# PLC20_breakout.net
KiCad netlist of a schematic drawn in EAGLE
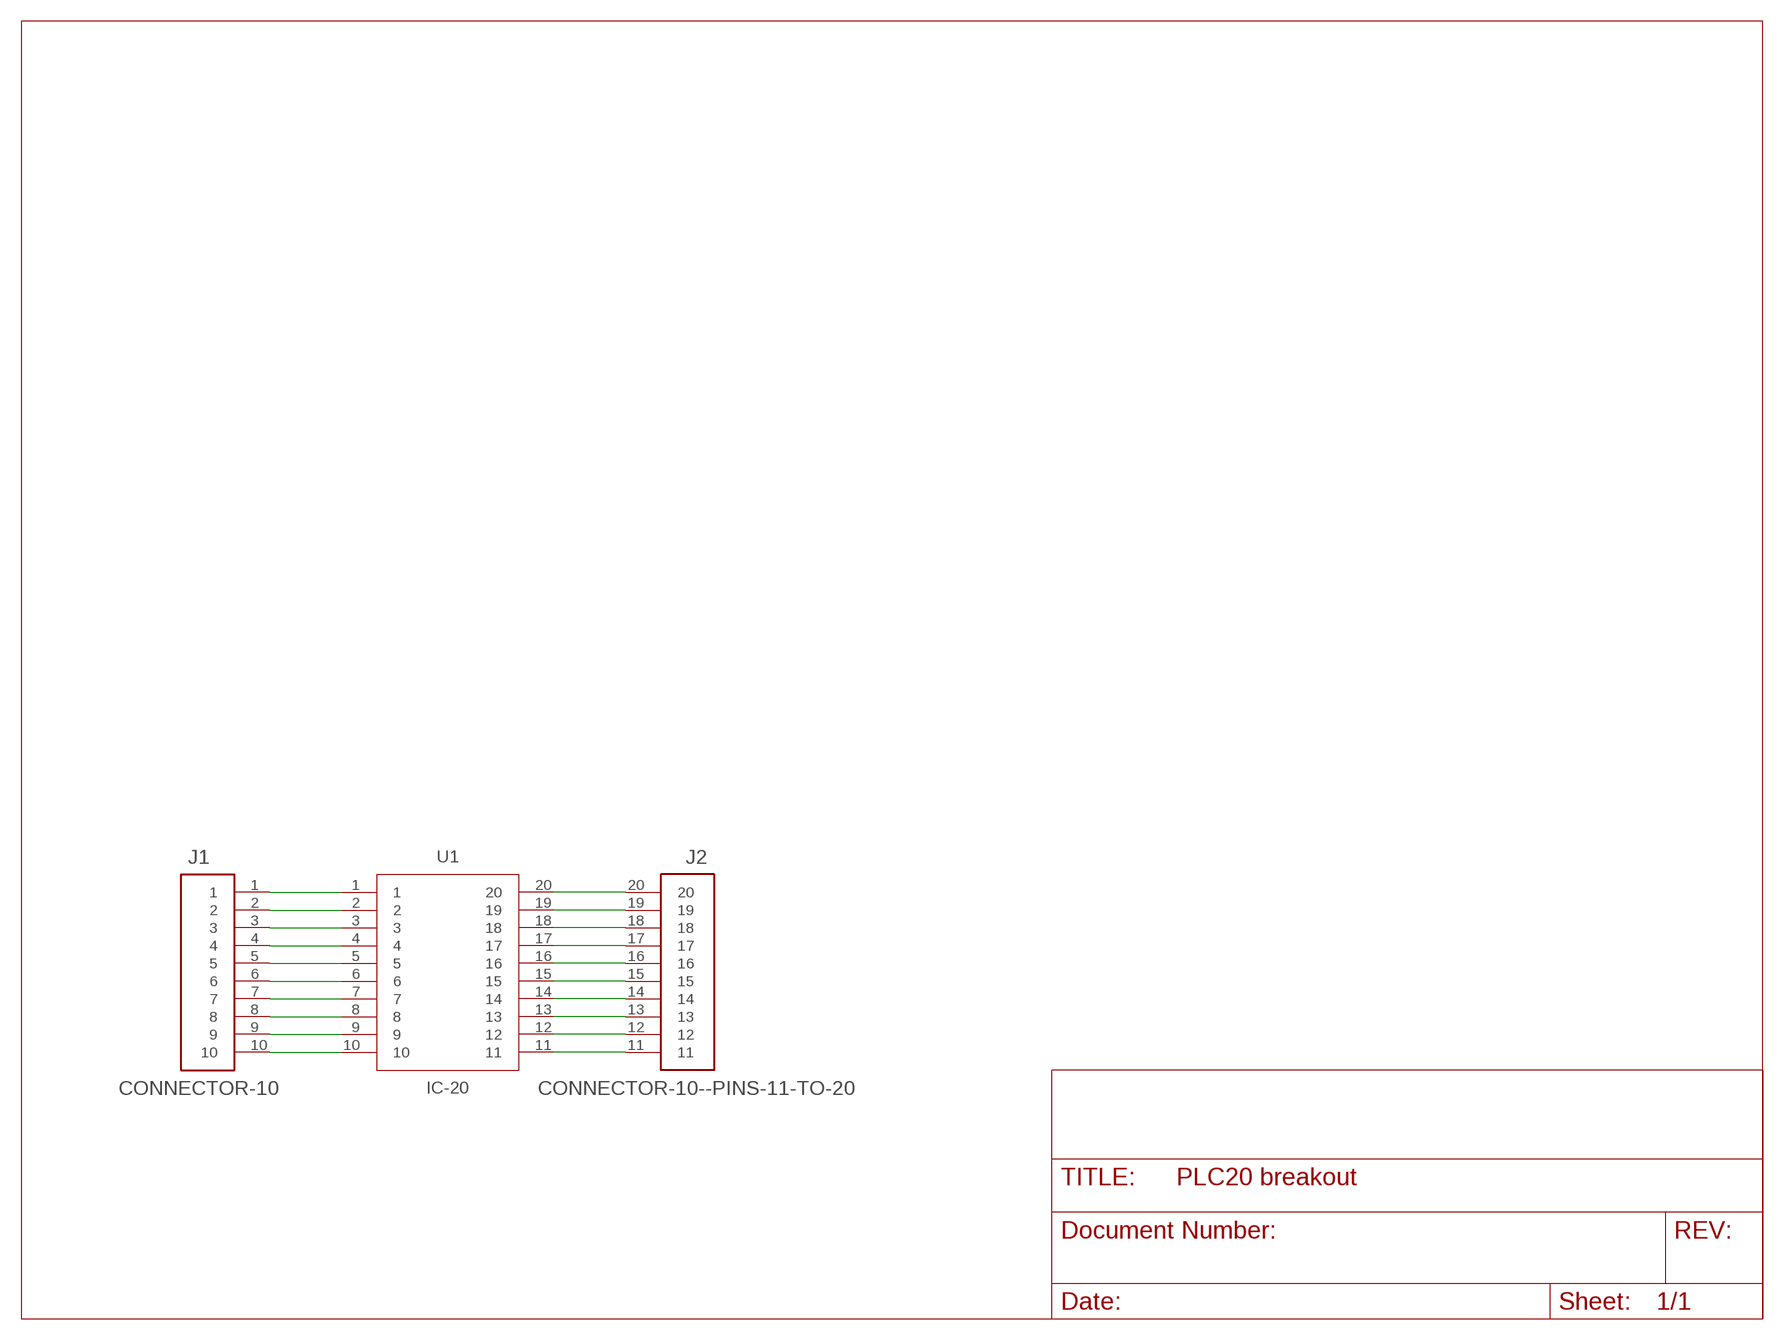
[diagram p0: schematic, sheet 1]

(export (version "E")
  (design (tool "Eeschema 10.0.6"))
  (components
    (comp (ref "J1")
      (value "CONNECTOR-10")
      (footprint "eagle-import:ESQ-110-XX-XX-S")
      (libsource (lib "eagle-import") (part "CONNECTOR-10"))
    )
    (comp (ref "J2")
      (value "CONNECTOR-10--PINS-11-TO-20")
      (footprint "eagle-import:ESQ-110-XX-XX-S--ROUND-PIN-1")
      (libsource (lib "eagle-import") (part "CONNECTOR-10--PINS-11-TO-20"))
    )
    (comp (ref "U1")
      (value "IC-20")
      (footprint "eagle-import:PLCC127P990X990X457-20N")
      (libsource (lib "eagle-import") (part "IC-20"))
    )
  )
  (nets
    (net (code "1") (name "Net-(J1-Pad1)") (class "Default")
      (node (ref "J1") (pin "1") (pinfunction "1_1") (pintype "bidirectional"))
      (node (ref "U1") (pin "1") (pinfunction "1_1") (pintype "bidirectional"))
    )
    (net (code "2") (name "Net-(J1-Pad2)") (class "Default")
      (node (ref "J1") (pin "2") (pinfunction "2_2") (pintype "bidirectional"))
      (node (ref "U1") (pin "2") (pinfunction "2_2") (pintype "bidirectional"))
    )
    (net (code "3") (name "Net-(J1-Pad3)") (class "Default")
      (node (ref "J1") (pin "3") (pinfunction "3_3") (pintype "bidirectional"))
      (node (ref "U1") (pin "3") (pinfunction "3_3") (pintype "bidirectional"))
    )
    (net (code "4") (name "Net-(J1-Pad4)") (class "Default")
      (node (ref "J1") (pin "4") (pinfunction "4_4") (pintype "bidirectional"))
      (node (ref "U1") (pin "4") (pinfunction "4_4") (pintype "bidirectional"))
    )
    (net (code "5") (name "Net-(J1-Pad5)") (class "Default")
      (node (ref "J1") (pin "5") (pinfunction "5_5") (pintype "bidirectional"))
      (node (ref "U1") (pin "5") (pinfunction "5_5") (pintype "bidirectional"))
    )
    (net (code "6") (name "Net-(J1-Pad6)") (class "Default")
      (node (ref "J1") (pin "6") (pinfunction "6_6") (pintype "bidirectional"))
      (node (ref "U1") (pin "6") (pinfunction "6_6") (pintype "bidirectional"))
    )
    (net (code "7") (name "Net-(J1-Pad7)") (class "Default")
      (node (ref "J1") (pin "7") (pinfunction "7_7") (pintype "bidirectional"))
      (node (ref "U1") (pin "7") (pinfunction "7_7") (pintype "bidirectional"))
    )
    (net (code "8") (name "Net-(J1-Pad8)") (class "Default")
      (node (ref "J1") (pin "8") (pinfunction "8_8") (pintype "bidirectional"))
      (node (ref "U1") (pin "8") (pinfunction "8_8") (pintype "bidirectional"))
    )
    (net (code "9") (name "Net-(J1-Pad9)") (class "Default")
      (node (ref "J1") (pin "9") (pinfunction "9_9") (pintype "bidirectional"))
      (node (ref "U1") (pin "9") (pinfunction "9_9") (pintype "bidirectional"))
    )
    (net (code "10") (name "Net-(J1-Pad10)") (class "Default")
      (node (ref "J1") (pin "10") (pinfunction "10_10") (pintype "bidirectional"))
      (node (ref "U1") (pin "10") (pinfunction "10_10") (pintype "bidirectional"))
    )
    (net (code "11") (name "Net-(J2-Pad11)") (class "Default")
      (node (ref "J2") (pin "11") (pinfunction "11_11") (pintype "bidirectional"))
      (node (ref "U1") (pin "11") (pinfunction "11_11") (pintype "bidirectional"))
    )
    (net (code "12") (name "Net-(J2-Pad12)") (class "Default")
      (node (ref "J2") (pin "12") (pinfunction "12_12") (pintype "bidirectional"))
      (node (ref "U1") (pin "12") (pinfunction "12_12") (pintype "bidirectional"))
    )
    (net (code "13") (name "Net-(J2-Pad13)") (class "Default")
      (node (ref "J2") (pin "13") (pinfunction "13_13") (pintype "bidirectional"))
      (node (ref "U1") (pin "13") (pinfunction "13_13") (pintype "bidirectional"))
    )
    (net (code "14") (name "Net-(J2-Pad14)") (class "Default")
      (node (ref "J2") (pin "14") (pinfunction "14_14") (pintype "bidirectional"))
      (node (ref "U1") (pin "14") (pinfunction "14_14") (pintype "bidirectional"))
    )
    (net (code "15") (name "Net-(J2-Pad15)") (class "Default")
      (node (ref "J2") (pin "15") (pinfunction "15_15") (pintype "bidirectional"))
      (node (ref "U1") (pin "15") (pinfunction "15_15") (pintype "bidirectional"))
    )
    (net (code "16") (name "Net-(J2-Pad16)") (class "Default")
      (node (ref "J2") (pin "16") (pinfunction "16_16") (pintype "bidirectional"))
      (node (ref "U1") (pin "16") (pinfunction "16_16") (pintype "bidirectional"))
    )
    (net (code "17") (name "Net-(J2-Pad17)") (class "Default")
      (node (ref "J2") (pin "17") (pinfunction "17_17") (pintype "bidirectional"))
      (node (ref "U1") (pin "17") (pinfunction "17_17") (pintype "bidirectional"))
    )
    (net (code "18") (name "Net-(J2-Pad18)") (class "Default")
      (node (ref "J2") (pin "18") (pinfunction "18_18") (pintype "bidirectional"))
      (node (ref "U1") (pin "18") (pinfunction "18_18") (pintype "bidirectional"))
    )
    (net (code "19") (name "Net-(J2-Pad19)") (class "Default")
      (node (ref "J2") (pin "19") (pinfunction "19_19") (pintype "bidirectional"))
      (node (ref "U1") (pin "19") (pinfunction "19_19") (pintype "bidirectional"))
    )
    (net (code "20") (name "Net-(J2-Pad20)") (class "Default")
      (node (ref "J2") (pin "20") (pinfunction "20_20") (pintype "bidirectional"))
      (node (ref "U1") (pin "20") (pinfunction "20_20") (pintype "bidirectional"))
    )
  )
)
